# Outputs.net
KiCad netlist of a schematic drawn in Altium Designer
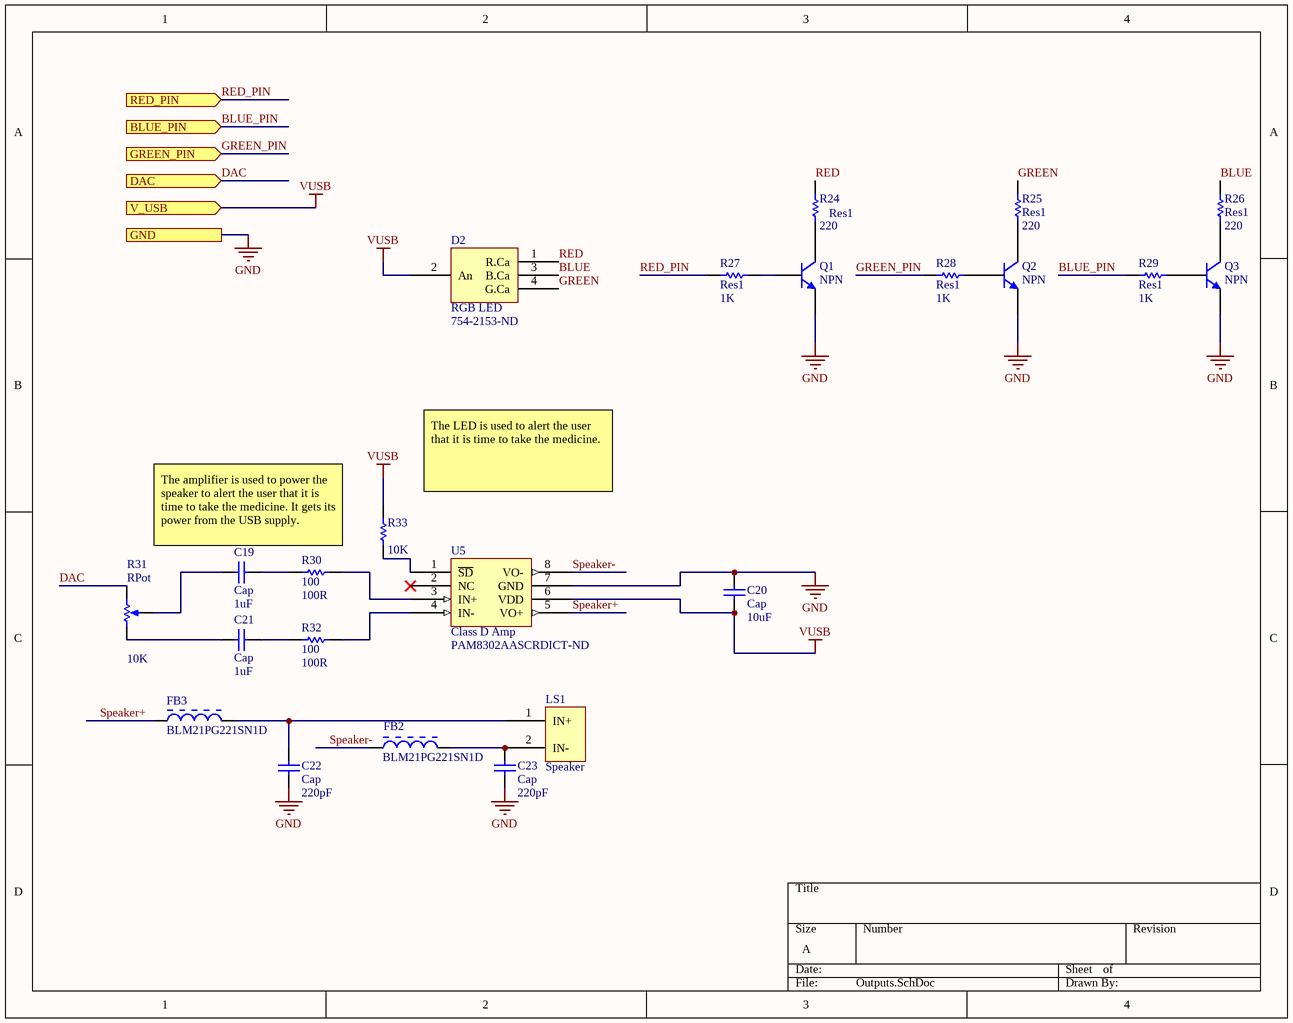
[diagram p0: Outputs.SchDoc]

(export (version "E")
  (design (tool "Eeschema 10.0.6"))
  (components
    (comp (ref "C19")
      (value "Cap")
      (footprint "C0805")
      (description "Capacitor")
      (fields (field (name "ALTIUM_VALUE") "1uF") (field (name "PUBLISHER") "Altium Limited"))
      (libsource (lib "Miscellaneous Devices") (part "Cap"))
    )
    (comp (ref "C20")
      (value "Cap")
      (footprint "1608[0603]")
      (description "Capacitor")
      (fields (field (name "ALTIUM_VALUE") "10uF") (field (name "PUBLISHER") "Altium Limited"))
      (libsource (lib "Miscellaneous Devices") (part "Cap"))
    )
    (comp (ref "C21")
      (value "Cap")
      (footprint "C0805")
      (description "Capacitor")
      (fields (field (name "ALTIUM_VALUE") "1uF") (field (name "PUBLISHER") "Altium Limited"))
      (libsource (lib "Miscellaneous Devices") (part "Cap"))
    )
    (comp (ref "C22")
      (value "Cap")
      (footprint "1608[0603]")
      (description "Capacitor")
      (fields (field (name "ALTIUM_VALUE") "220pF") (field (name "PUBLISHER") "Altium Limited"))
      (libsource (lib "Miscellaneous Devices") (part "Cap"))
    )
    (comp (ref "C23")
      (value "Cap")
      (footprint "1608[0603]")
      (description "Capacitor")
      (fields (field (name "ALTIUM_VALUE") "220pF") (field (name "PUBLISHER") "Altium Limited"))
      (libsource (lib "Miscellaneous Devices") (part "Cap"))
    )
    (comp (ref "D2")
      (value "RGB LED")
      (footprint "WP154A4 LED")
      (description "RGB LED (THT)")
      (fields
        (field (name "MANUFACTURER") "Kingbright")
        (field (name "MANUFACTURER PART NUMBER") "WP154A4SEJ3VBDZGC/CA")
        (field (name "SUPPLIER PART NUMBER 1") "754-2153-ND")
      )
      (libsource (lib "Iot_Medicine") (part "WP154A4"))
    )
    (comp (ref "FB2")
      (value "BLM21PG221SN1D")
      (footprint "MURA-BLM21-B20-CHIP-2_V1")
      (fields (field (name "MANUFACTURER") "Murata"))
      (libsource (lib "Altium Content Vault") (part "MURA-FB-2"))
    )
    (comp (ref "FB3")
      (value "BLM21PG221SN1D")
      (footprint "MURA-BLM21-B20-CHIP-2_V1")
      (fields (field (name "MANUFACTURER") "Murata"))
      (libsource (lib "Altium Content Vault") (part "MURA-FB-2"))
    )
    (comp (ref "LS1")
      (value "Speaker")
      (footprint "Speaker")
      (description "Speaker 3\" Diameter 4 Ohm 3 Watt")
      (libsource (lib "Iot_Medicine") (part "Adafruit 3{dblquote} Speaker"))
    )
    (comp (ref "Q1")
      (value "NPN")
      (footprint "SOT23_L")
      (description "NPN Bipolar Transistor")
      (fields (field (name "PUBLISHER") "Altium Limited"))
      (libsource (lib "Miscellaneous Devices") (part "NPN"))
    )
    (comp (ref "Q2")
      (value "NPN")
      (footprint "SOT23_L")
      (description "NPN Bipolar Transistor")
      (fields (field (name "PUBLISHER") "Altium Limited"))
      (libsource (lib "Miscellaneous Devices") (part "NPN"))
    )
    (comp (ref "Q3")
      (value "NPN")
      (footprint "SOT23_L")
      (description "NPN Bipolar Transistor")
      (fields (field (name "PUBLISHER") "Altium Limited"))
      (libsource (lib "Miscellaneous Devices") (part "NPN"))
    )
    (comp (ref "R24")
      (value "Res1")
      (footprint "6-0805_L")
      (description "Resistor")
      (fields (field (name "ALTIUM_VALUE") "220") (field (name "PUBLISHER") "Altium Limited"))
      (libsource (lib "Miscellaneous Devices") (part "Res1"))
    )
    (comp (ref "R25")
      (value "Res1")
      (footprint "6-0805_L")
      (description "Resistor")
      (fields (field (name "ALTIUM_VALUE") "220") (field (name "PUBLISHER") "Altium Limited"))
      (libsource (lib "Miscellaneous Devices") (part "Res1"))
    )
    (comp (ref "R26")
      (value "Res1")
      (footprint "6-0805_L")
      (description "Resistor")
      (fields (field (name "ALTIUM_VALUE") "220") (field (name "PUBLISHER") "Altium Limited"))
      (libsource (lib "Miscellaneous Devices") (part "Res1"))
    )
    (comp (ref "R27")
      (value "Res1")
      (footprint "J1-0603")
      (description "Resistor")
      (fields (field (name "ALTIUM_VALUE") "1K") (field (name "PUBLISHER") "Altium Limited"))
      (libsource (lib "Miscellaneous Devices") (part "Res1"))
    )
    (comp (ref "R28")
      (value "Res1")
      (footprint "J1-0603")
      (description "Resistor")
      (fields (field (name "ALTIUM_VALUE") "1K") (field (name "PUBLISHER") "Altium Limited"))
      (libsource (lib "Miscellaneous Devices") (part "Res1"))
    )
    (comp (ref "R29")
      (value "Res1")
      (footprint "J1-0603")
      (description "Resistor")
      (fields (field (name "ALTIUM_VALUE") "1K") (field (name "PUBLISHER") "Altium Limited"))
      (libsource (lib "Miscellaneous Devices") (part "Res1"))
    )
    (comp (ref "R30")
      (value "100")
      (footprint "6-0805_L")
      (description "Resistor (100)")
      (fields (field (name "ALTIUM_VALUE") "100R") (field (name "PUBLISHER") "Altium Limited"))
      (libsource (lib "Miscellaneous Devices") (part "Res1"))
    )
    (comp (ref "R31")
      (value "RPot")
      (footprint "VR4")
      (description "Potentiometer")
      (fields (field (name "ALTIUM_VALUE") "10K") (field (name "PUBLISHER") "Altium Limited"))
      (libsource (lib "Miscellaneous Devices") (part "RPot"))
    )
    (comp (ref "R32")
      (value "100")
      (footprint "6-0805_L")
      (description "Resistor (100)")
      (fields (field (name "ALTIUM_VALUE") "100R") (field (name "PUBLISHER") "Altium Limited"))
      (libsource (lib "Miscellaneous Devices") (part "Res1"))
    )
    (comp (ref "R33")
      (value "10K")
      (footprint "J1-0603")
      (description "Resistor")
      (fields (field (name "PUBLISHER") "Altium Limited"))
      (libsource (lib "Miscellaneous Devices") (part "Res1"))
    )
    (comp (ref "U5")
      (value "Class D Amp")
      (footprint "PAM8302 SO-8")
      (description "2.5W Filterless Class-D Mono Audio Amplifier")
      (fields
        (field (name "MANUFACTURER") "Diodes")
        (field (name "MANUFACTURER PART NUMBER") "PAM8302AADCR")
        (field (name "SUPPLIER PART NUMBER 1") "PAM8302AASCRDICT-ND")
      )
      (libsource (lib "Iot_Medicine") (part "PAM8302A"))
    )
  )
  (nets
    (net (code "1") (name "/BLUE") (class "Default")
      (node (ref "D2") (pin "3") (pinfunction "B.Ca_3") (pintype "passive"))
      (node (ref "R26") (pin "2") (pinfunction "2_2") (pintype "passive"))
    )
    (net (code "2") (name "/BLUE_PIN") (class "Default")
      (node (ref "R29") (pin "1") (pinfunction "1_1") (pintype "passive"))
    )
    (net (code "3") (name "/DAC") (class "Default")
      (node (ref "R31") (pin "2") (pinfunction "BOT_2") (pintype "passive"))
    )
    (net (code "4") (name "/GREEN") (class "Default")
      (node (ref "D2") (pin "4") (pinfunction "G.Ca_4") (pintype "passive"))
      (node (ref "R25") (pin "2") (pinfunction "2_2") (pintype "passive"))
    )
    (net (code "5") (name "/GREEN_PIN") (class "Default")
      (node (ref "R28") (pin "1") (pinfunction "1_1") (pintype "passive"))
    )
    (net (code "6") (name "/RED") (class "Default")
      (node (ref "D2") (pin "1") (pinfunction "R.Ca_1") (pintype "passive"))
      (node (ref "R24") (pin "2") (pinfunction "2_2") (pintype "passive"))
    )
    (net (code "7") (name "/RED_PIN") (class "Default")
      (node (ref "R27") (pin "1") (pinfunction "1_1") (pintype "passive"))
    )
    (net (code "8") (name "/Speaker+") (class "Default")
      (node (ref "FB3") (pin "1") (pinfunction "1_1") (pintype "passive"))
      (node (ref "U5") (pin "5") (pinfunction "VO+_5") (pintype "output"))
    )
    (net (code "9") (name "/Speaker-") (class "Default")
      (node (ref "FB2") (pin "1") (pinfunction "1_1") (pintype "passive"))
      (node (ref "U5") (pin "8") (pinfunction "VO-_8") (pintype "output"))
    )
    (net (code "10") (name "GND") (class "Default")
      (node (ref "C20") (pin "2") (pinfunction "2_2") (pintype "passive"))
      (node (ref "C22") (pin "2") (pinfunction "2_2") (pintype "passive"))
      (node (ref "C23") (pin "1") (pinfunction "1_1") (pintype "passive"))
      (node (ref "Q1") (pin "3") (pinfunction "E_3") (pintype "passive"))
      (node (ref "Q2") (pin "3") (pinfunction "E_3") (pintype "passive"))
      (node (ref "Q3") (pin "3") (pinfunction "E_3") (pintype "passive"))
      (node (ref "U5") (pin "7") (pinfunction "GND_7") (pintype "power_in"))
    )
    (net (code "11") (name "Net-(C19-Pad2)") (class "Default")
      (node (ref "C19") (pin "2") (pinfunction "2_2") (pintype "passive"))
      (node (ref "R30") (pin "1") (pinfunction "1_1") (pintype "passive"))
    )
    (net (code "12") (name "Net-(C21-Pad2)") (class "Default")
      (node (ref "C21") (pin "2") (pinfunction "2_2") (pintype "passive"))
      (node (ref "R32") (pin "1") (pinfunction "1_1") (pintype "passive"))
    )
    (net (code "13") (name "Net-(LS1-IN+)") (class "Default")
      (node (ref "C22") (pin "1") (pinfunction "1_1") (pintype "passive"))
      (node (ref "FB3") (pin "2") (pinfunction "2_2") (pintype "passive"))
      (node (ref "LS1") (pin "1") (pinfunction "IN+_1") (pintype "passive"))
    )
    (net (code "14") (name "Net-(LS1-IN-)") (class "Default")
      (node (ref "C23") (pin "2") (pinfunction "2_2") (pintype "passive"))
      (node (ref "FB2") (pin "2") (pinfunction "2_2") (pintype "passive"))
      (node (ref "LS1") (pin "2") (pinfunction "IN-_2") (pintype "passive"))
    )
    (net (code "15") (name "Net-(Q1-B)") (class "Default")
      (node (ref "Q1") (pin "2") (pinfunction "B_2") (pintype "passive"))
      (node (ref "R27") (pin "2") (pinfunction "2_2") (pintype "passive"))
    )
    (net (code "16") (name "Net-(Q1-C)") (class "Default")
      (node (ref "Q1") (pin "1") (pinfunction "C_1") (pintype "passive"))
      (node (ref "R24") (pin "1") (pinfunction "1_1") (pintype "passive"))
    )
    (net (code "17") (name "Net-(Q2-B)") (class "Default")
      (node (ref "Q2") (pin "2") (pinfunction "B_2") (pintype "passive"))
      (node (ref "R28") (pin "2") (pinfunction "2_2") (pintype "passive"))
    )
    (net (code "18") (name "Net-(Q2-C)") (class "Default")
      (node (ref "Q2") (pin "1") (pinfunction "C_1") (pintype "passive"))
      (node (ref "R25") (pin "1") (pinfunction "1_1") (pintype "passive"))
    )
    (net (code "19") (name "Net-(Q3-B)") (class "Default")
      (node (ref "Q3") (pin "2") (pinfunction "B_2") (pintype "passive"))
      (node (ref "R29") (pin "2") (pinfunction "2_2") (pintype "passive"))
    )
    (net (code "20") (name "Net-(Q3-C)") (class "Default")
      (node (ref "Q3") (pin "1") (pinfunction "C_1") (pintype "passive"))
      (node (ref "R26") (pin "1") (pinfunction "1_1") (pintype "passive"))
    )
    (net (code "21") (name "Net-(R31-TAP)") (class "Default")
      (node (ref "C19") (pin "1") (pinfunction "1_1") (pintype "passive"))
      (node (ref "R31") (pin "3") (pinfunction "TAP_3") (pintype "passive"))
    )
    (net (code "22") (name "Net-(R31-TOP)") (class "Default")
      (node (ref "C21") (pin "1") (pinfunction "1_1") (pintype "passive"))
      (node (ref "R31") (pin "1") (pinfunction "TOP_1") (pintype "passive"))
    )
    (net (code "23") (name "Net-(U5-IN+)") (class "Default")
      (node (ref "R30") (pin "2") (pinfunction "2_2") (pintype "passive"))
      (node (ref "U5") (pin "3") (pinfunction "IN+_3") (pintype "input"))
    )
    (net (code "24") (name "Net-(U5-IN-)") (class "Default")
      (node (ref "R32") (pin "2") (pinfunction "2_2") (pintype "passive"))
      (node (ref "U5") (pin "4") (pinfunction "IN-_4") (pintype "input"))
    )
    (net (code "25") (name "Net-(U5-~{SD})") (class "Default")
      (node (ref "R33") (pin "1") (pinfunction "1_1") (pintype "passive"))
      (node (ref "U5") (pin "1") (pinfunction "~{SD}_1") (pintype "passive"))
    )
    (net (code "26") (name "VUSB") (class "Default")
      (node (ref "C20") (pin "1") (pinfunction "1_1") (pintype "passive"))
      (node (ref "D2") (pin "2") (pinfunction "An_2") (pintype "passive"))
      (node (ref "R33") (pin "2") (pinfunction "2_2") (pintype "passive"))
      (node (ref "U5") (pin "6") (pinfunction "VDD_6") (pintype "power_in"))
    )
    (net (code "27") (name "unconnected-(U5-NC-Pad2)") (class "Default")
      (node (ref "U5") (pin "2") (pinfunction "NC_2") (pintype "passive+no_connect"))
    )
  )
)
